# mini_breakout_with_chip_100kx2.net
KiCad netlist of a schematic drawn in EAGLE
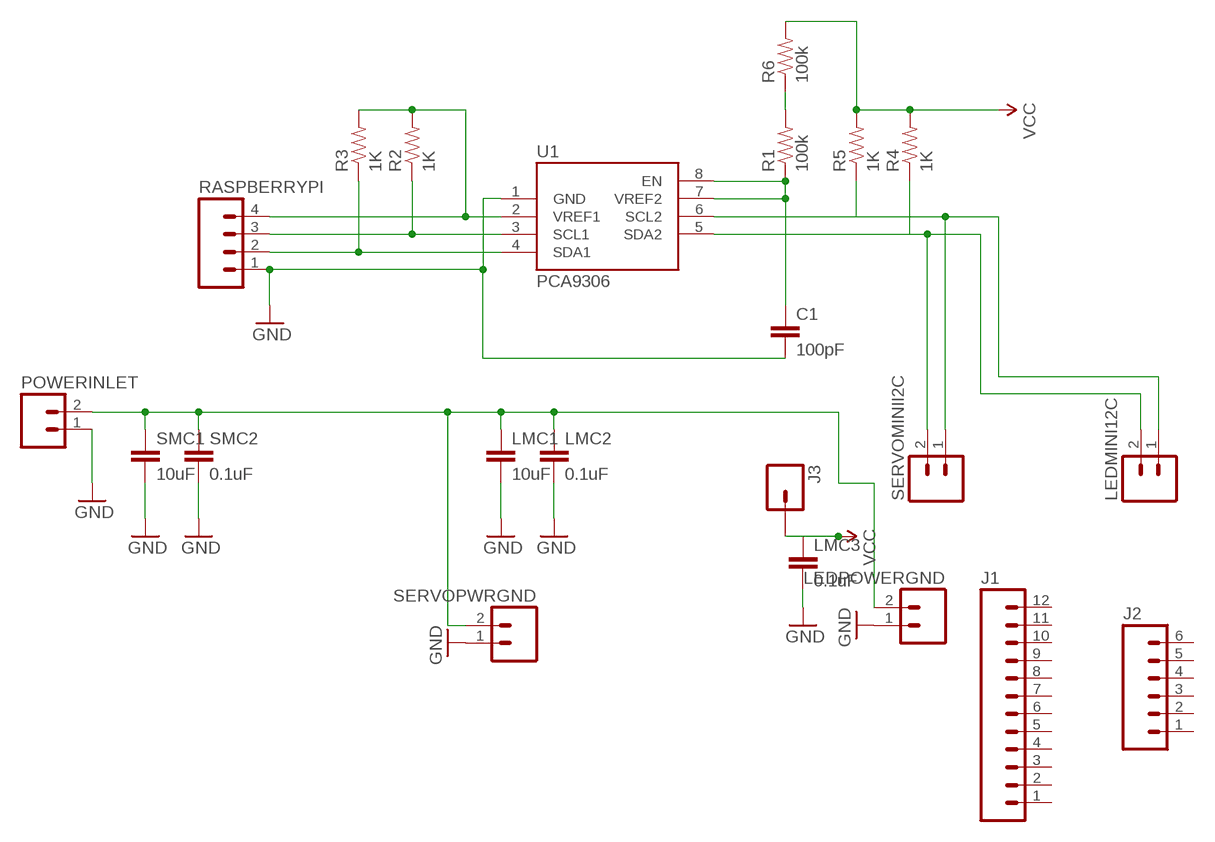
[diagram p0: schematic, sheet 1]

(export (version "E")
  (design (tool "Eeschema 10.0.6"))
  (components
    (comp (ref "C1")
      (value "100pF")
      (footprint "eagle-import:0603-CAP")
      (libsource (lib "eagle-import") (part "100PF-50V-5%(0603)"))
    )
    (comp (ref "J1")
      (value "M121X12_NO_SILK_KIT")
      (footprint "eagle-import:1X12_NO_SILK_KIT")
      (libsource (lib "eagle-import") (part "M121X12_NO_SILK_KIT"))
    )
    (comp (ref "J2")
      (value "M06NO_SILK_YES_STOP")
      (footprint "eagle-import:1X06_NO_SILK_YES_STOP")
      (libsource (lib "eagle-import") (part "M06NO_SILK_YES_STOP"))
    )
    (comp (ref "J3")
      (value "M01NOSILK-KIT")
      (footprint "eagle-import:1X01NS-KIT")
      (libsource (lib "eagle-import") (part "M01NOSILK-KIT"))
    )
    (comp (ref "LEDMINI12C")
      (value "M02PTH")
      (footprint "eagle-import:1X02")
      (libsource (lib "eagle-import") (part "M02PTH"))
    )
    (comp (ref "LEDPOWERGND")
      (value "M021X02_NO_SILK")
      (footprint "eagle-import:1X02_NO_SILK")
      (libsource (lib "eagle-import") (part "M021X02_NO_SILK"))
    )
    (comp (ref "LMC1")
      (value "10uF")
      (footprint "eagle-import:0603-CAP")
      (libsource (lib "eagle-import") (part "10UF-6.3V-20%(0603)"))
    )
    (comp (ref "LMC2")
      (value "0.1uF")
      (footprint "eagle-import:0603-CAP")
      (libsource (lib "eagle-import") (part "0.1UF-25V-5%(0603)"))
    )
    (comp (ref "LMC3")
      (value "0.1uF")
      (footprint "eagle-import:0603-CAP")
      (libsource (lib "eagle-import") (part "0.1UF-25V-5%(0603)"))
    )
    (comp (ref "POWERINLET")
      (value "M02PTH")
      (footprint "eagle-import:1X02")
      (libsource (lib "eagle-import") (part "M02PTH"))
    )
    (comp (ref "R1")
      (value "100k")
      (footprint "eagle-import:0603-RES")
      (libsource (lib "eagle-import") (part "100KOHM-1/10W-1%(0603)"))
    )
    (comp (ref "R2")
      (value "1K")
      (footprint "eagle-import:0603-RES")
      (libsource (lib "eagle-import") (part "1KOHM-1/10W-1%(0603)"))
    )
    (comp (ref "R3")
      (value "1K")
      (footprint "eagle-import:0603-RES")
      (libsource (lib "eagle-import") (part "1KOHM-1/10W-1%(0603)"))
    )
    (comp (ref "R4")
      (value "1K")
      (footprint "eagle-import:0603-RES")
      (libsource (lib "eagle-import") (part "1KOHM-1/10W-1%(0603)"))
    )
    (comp (ref "R5")
      (value "1K")
      (footprint "eagle-import:0603-RES")
      (libsource (lib "eagle-import") (part "1KOHM-1/10W-1%(0603)"))
    )
    (comp (ref "R6")
      (value "100k")
      (footprint "eagle-import:0603-RES")
      (libsource (lib "eagle-import") (part "100KOHM-1/10W-1%(0603)"))
    )
    (comp (ref "RASPBERRYPI")
      (value "M04PTH")
      (footprint "eagle-import:1X04")
      (libsource (lib "eagle-import") (part "M04PTH"))
    )
    (comp (ref "SERVOMINII2C")
      (value "M02PTH")
      (footprint "eagle-import:1X02")
      (libsource (lib "eagle-import") (part "M02PTH"))
    )
    (comp (ref "SERVOPWRGND")
      (value "M021X02_NO_SILK")
      (footprint "eagle-import:1X02_NO_SILK")
      (libsource (lib "eagle-import") (part "M021X02_NO_SILK"))
    )
    (comp (ref "SMC1")
      (value "10uF")
      (footprint "eagle-import:0603-CAP")
      (libsource (lib "eagle-import") (part "10UF-6.3V-20%(0603)"))
    )
    (comp (ref "SMC2")
      (value "0.1uF")
      (footprint "eagle-import:0603-CAP")
      (libsource (lib "eagle-import") (part "0.1UF-25V-5%(0603)"))
    )
    (comp (ref "U1")
      (value "PCA9306")
      (footprint "eagle-import:PSOP-8")
      (libsource (lib "eagle-import") (part "PCA9306"))
    )
  )
  (nets
    (net (code "1") (name "GND") (class "Default")
      (node (ref "C1") (pin "2") (pinfunction "2_2") (pintype "passive"))
      (node (ref "LEDPOWERGND") (pin "1") (pinfunction "1_1") (pintype "passive"))
      (node (ref "LMC1") (pin "2") (pinfunction "2_2") (pintype "passive"))
      (node (ref "LMC2") (pin "2") (pinfunction "2_2") (pintype "passive"))
      (node (ref "LMC3") (pin "2") (pinfunction "2_2") (pintype "passive"))
      (node (ref "POWERINLET") (pin "1") (pinfunction "1_1") (pintype "passive"))
      (node (ref "RASPBERRYPI") (pin "1") (pinfunction "1_1") (pintype "passive"))
      (node (ref "SERVOPWRGND") (pin "1") (pinfunction "1_1") (pintype "passive"))
      (node (ref "SMC1") (pin "2") (pinfunction "2_2") (pintype "passive"))
      (node (ref "SMC2") (pin "2") (pinfunction "2_2") (pintype "passive"))
      (node (ref "U1") (pin "1") (pinfunction "GND_1") (pintype "bidirectional"))
    )
    (net (code "2") (name "Net-(LEDPOWERGND-Pad2)") (class "Default")
      (node (ref "LEDPOWERGND") (pin "2") (pinfunction "2_2") (pintype "passive"))
      (node (ref "LMC1") (pin "1") (pinfunction "1_1") (pintype "passive"))
      (node (ref "LMC2") (pin "1") (pinfunction "1_1") (pintype "passive"))
      (node (ref "POWERINLET") (pin "2") (pinfunction "2_2") (pintype "passive"))
      (node (ref "SERVOPWRGND") (pin "2") (pinfunction "2_2") (pintype "passive"))
      (node (ref "SMC1") (pin "1") (pinfunction "1_1") (pintype "passive"))
      (node (ref "SMC2") (pin "1") (pinfunction "1_1") (pintype "passive"))
    )
    (net (code "3") (name "Net-(R1-Pad2)") (class "Default")
      (node (ref "R1") (pin "2") (pinfunction "2_2") (pintype "passive"))
      (node (ref "R6") (pin "1") (pinfunction "1_1") (pintype "passive"))
    )
    (net (code "4") (name "Net-(U1-EN)") (class "Default")
      (node (ref "C1") (pin "1") (pinfunction "1_1") (pintype "passive"))
      (node (ref "R1") (pin "1") (pinfunction "1_1") (pintype "passive"))
      (node (ref "U1") (pin "7") (pinfunction "VREF2_7") (pintype "bidirectional"))
      (node (ref "U1") (pin "8") (pinfunction "EN_8") (pintype "bidirectional"))
    )
    (net (code "5") (name "Net-(U1-SCL1)") (class "Default")
      (node (ref "R2") (pin "1") (pinfunction "1_1") (pintype "passive"))
      (node (ref "RASPBERRYPI") (pin "3") (pinfunction "3_3") (pintype "passive"))
      (node (ref "U1") (pin "3") (pinfunction "SCL1_3") (pintype "bidirectional"))
    )
    (net (code "6") (name "Net-(U1-SCL2)") (class "Default")
      (node (ref "LEDMINI12C") (pin "1") (pinfunction "1_1") (pintype "passive"))
      (node (ref "R5") (pin "1") (pinfunction "1_1") (pintype "passive"))
      (node (ref "SERVOMINII2C") (pin "1") (pinfunction "1_1") (pintype "passive"))
      (node (ref "U1") (pin "6") (pinfunction "SCL2_6") (pintype "bidirectional"))
    )
    (net (code "7") (name "Net-(U1-SDA1)") (class "Default")
      (node (ref "R3") (pin "1") (pinfunction "1_1") (pintype "passive"))
      (node (ref "RASPBERRYPI") (pin "2") (pinfunction "2_2") (pintype "passive"))
      (node (ref "U1") (pin "4") (pinfunction "SDA1_4") (pintype "bidirectional"))
    )
    (net (code "8") (name "Net-(U1-SDA2)") (class "Default")
      (node (ref "LEDMINI12C") (pin "2") (pinfunction "2_2") (pintype "passive"))
      (node (ref "R4") (pin "1") (pinfunction "1_1") (pintype "passive"))
      (node (ref "SERVOMINII2C") (pin "2") (pinfunction "2_2") (pintype "passive"))
      (node (ref "U1") (pin "5") (pinfunction "SDA2_5") (pintype "bidirectional"))
    )
    (net (code "9") (name "Net-(U1-VREF1)") (class "Default")
      (node (ref "R2") (pin "2") (pinfunction "2_2") (pintype "passive"))
      (node (ref "R3") (pin "2") (pinfunction "2_2") (pintype "passive"))
      (node (ref "RASPBERRYPI") (pin "4") (pinfunction "4_4") (pintype "passive"))
      (node (ref "U1") (pin "2") (pinfunction "VREF1_2") (pintype "bidirectional"))
    )
    (net (code "10") (name "VCC") (class "Default")
      (node (ref "J3") (pin "1") (pinfunction "1_1") (pintype "passive"))
      (node (ref "LMC3") (pin "1") (pinfunction "1_1") (pintype "passive"))
      (node (ref "R4") (pin "2") (pinfunction "2_2") (pintype "passive"))
      (node (ref "R5") (pin "2") (pinfunction "2_2") (pintype "passive"))
      (node (ref "R6") (pin "2") (pinfunction "2_2") (pintype "passive"))
    )
    (net (code "11") (name "unconnected-(J1-Pad1)") (class "Default")
      (node (ref "J1") (pin "1") (pinfunction "1_1") (pintype "passive"))
    )
    (net (code "12") (name "unconnected-(J1-Pad2)") (class "Default")
      (node (ref "J1") (pin "2") (pinfunction "2_2") (pintype "passive"))
    )
    (net (code "13") (name "unconnected-(J1-Pad3)") (class "Default")
      (node (ref "J1") (pin "3") (pinfunction "3_3") (pintype "passive"))
    )
    (net (code "14") (name "unconnected-(J1-Pad4)") (class "Default")
      (node (ref "J1") (pin "4") (pinfunction "4_4") (pintype "passive"))
    )
    (net (code "15") (name "unconnected-(J1-Pad5)") (class "Default")
      (node (ref "J1") (pin "5") (pinfunction "5_5") (pintype "passive"))
    )
    (net (code "16") (name "unconnected-(J1-Pad6)") (class "Default")
      (node (ref "J1") (pin "6") (pinfunction "6_6") (pintype "passive"))
    )
    (net (code "17") (name "unconnected-(J1-Pad7)") (class "Default")
      (node (ref "J1") (pin "7") (pinfunction "7_7") (pintype "passive"))
    )
    (net (code "18") (name "unconnected-(J1-Pad8)") (class "Default")
      (node (ref "J1") (pin "8") (pinfunction "8_8") (pintype "passive"))
    )
    (net (code "19") (name "unconnected-(J1-Pad9)") (class "Default")
      (node (ref "J1") (pin "9") (pinfunction "9_9") (pintype "passive"))
    )
    (net (code "20") (name "unconnected-(J1-Pad10)") (class "Default")
      (node (ref "J1") (pin "10") (pinfunction "10_10") (pintype "passive"))
    )
    (net (code "21") (name "unconnected-(J1-Pad11)") (class "Default")
      (node (ref "J1") (pin "11") (pinfunction "11_11") (pintype "passive"))
    )
    (net (code "22") (name "unconnected-(J1-Pad12)") (class "Default")
      (node (ref "J1") (pin "12") (pinfunction "12_12") (pintype "passive"))
    )
    (net (code "23") (name "unconnected-(J2-Pad1)") (class "Default")
      (node (ref "J2") (pin "1") (pinfunction "1_1") (pintype "passive"))
    )
    (net (code "24") (name "unconnected-(J2-Pad2)") (class "Default")
      (node (ref "J2") (pin "2") (pinfunction "2_2") (pintype "passive"))
    )
    (net (code "25") (name "unconnected-(J2-Pad3)") (class "Default")
      (node (ref "J2") (pin "3") (pinfunction "3_3") (pintype "passive"))
    )
    (net (code "26") (name "unconnected-(J2-Pad4)") (class "Default")
      (node (ref "J2") (pin "4") (pinfunction "4_4") (pintype "passive"))
    )
    (net (code "27") (name "unconnected-(J2-Pad5)") (class "Default")
      (node (ref "J2") (pin "5") (pinfunction "5_5") (pintype "passive"))
    )
    (net (code "28") (name "unconnected-(J2-Pad6)") (class "Default")
      (node (ref "J2") (pin "6") (pinfunction "6_6") (pintype "passive"))
    )
  )
)
